# MovimientoALIM.net
KiCad netlist of a schematic drawn in EAGLE
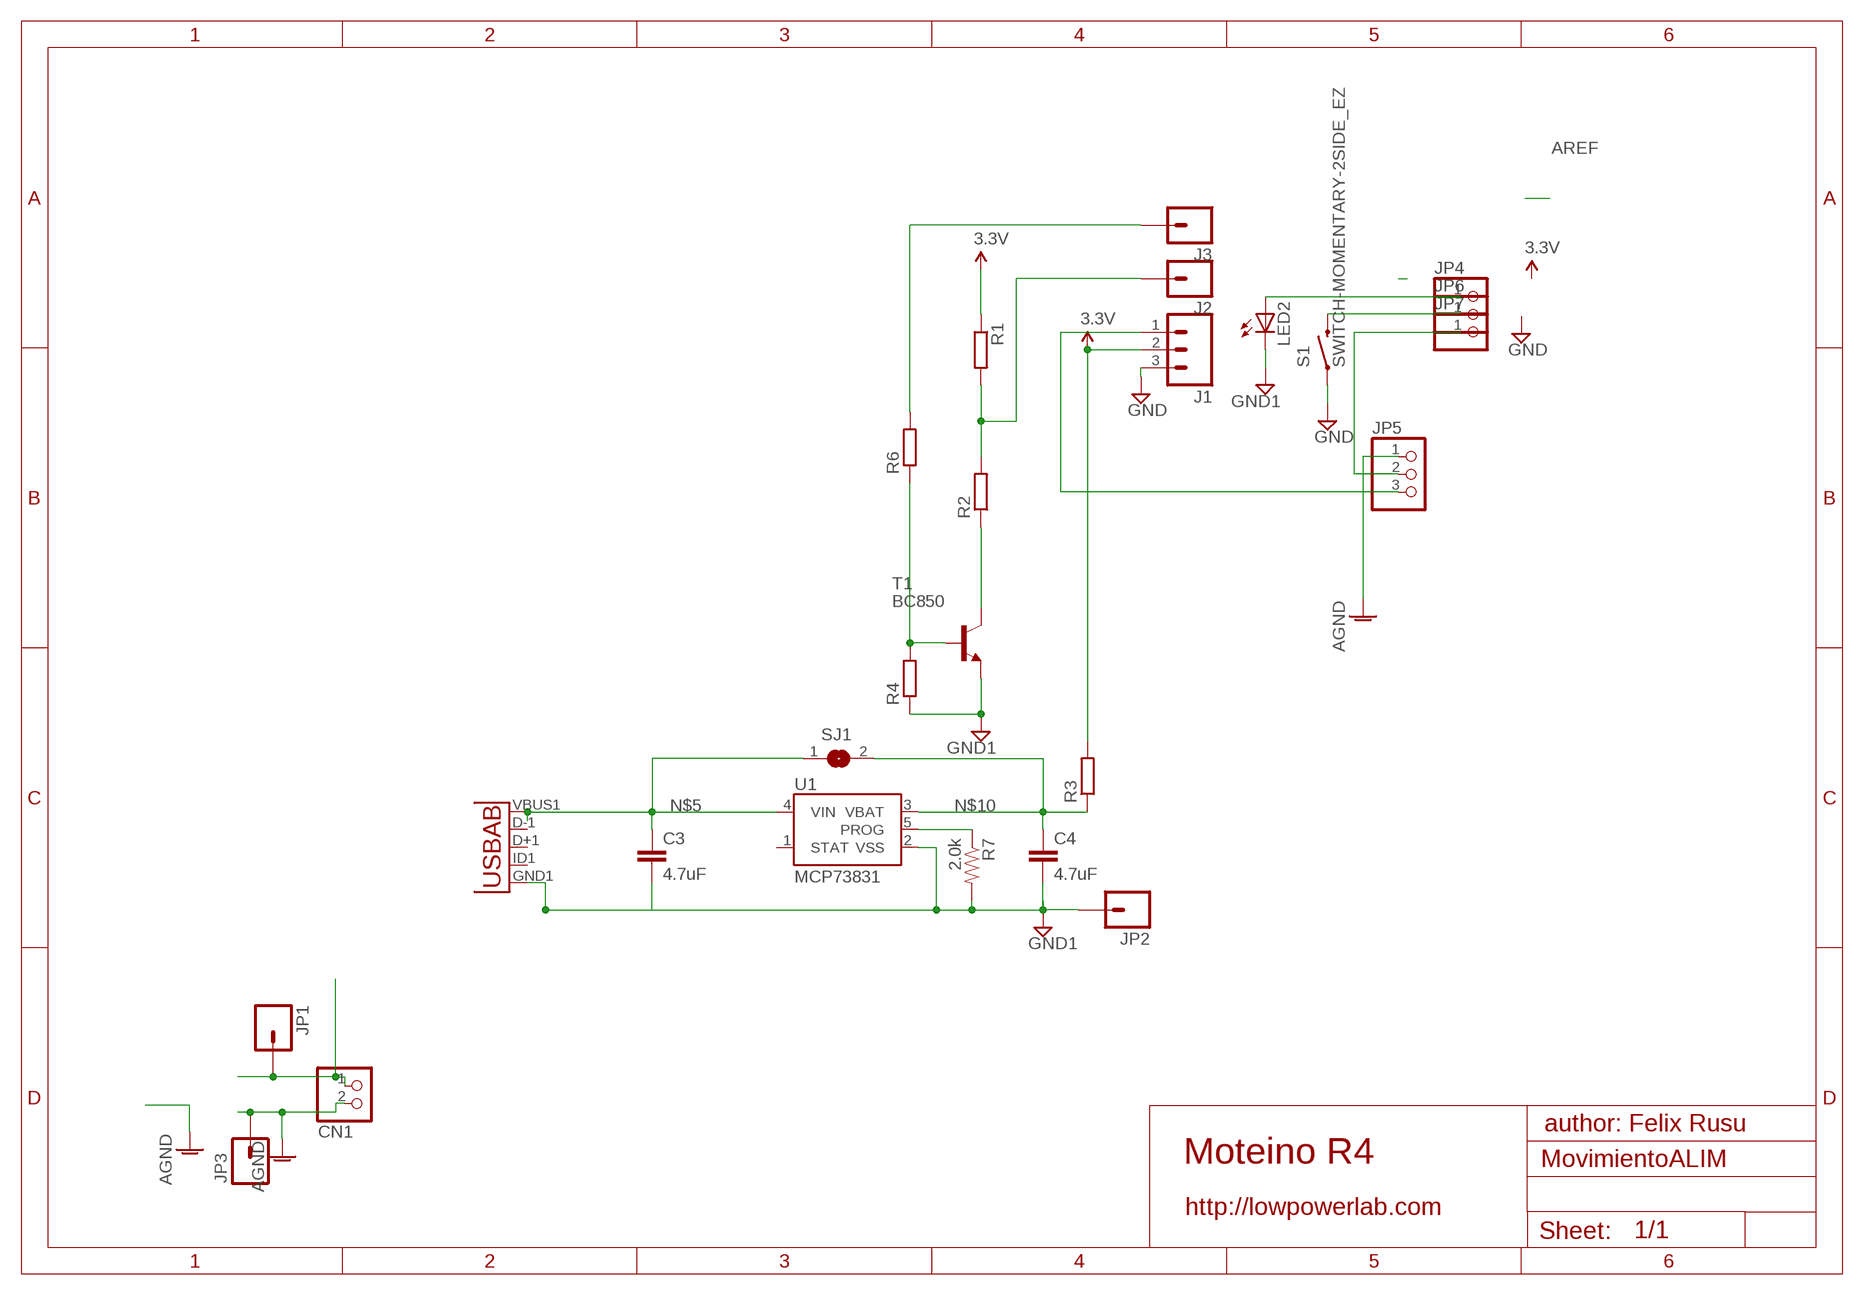
[diagram p0: schematic, sheet 1]

(export (version "E")
  (design (tool "Eeschema 10.0.6"))
  (components
    (comp (ref "C3")
      (value "4.7uF")
      (footprint "eagle-import:0603-CAP")
      (libsource (lib "eagle-import") (part "4.7UF-6.3V-10%(0603)0603"))
    )
    (comp (ref "C4")
      (value "4.7uF")
      (footprint "eagle-import:0603-CAP")
      (libsource (lib "eagle-import") (part "4.7UF-6.3V-10%(0603)0603"))
    )
    (comp (ref "CN1")
      (value "JST_2PIN-SMT")
      (footprint "eagle-import:JST-PH-2-SMT")
      (libsource (lib "eagle-import") (part "JST_2PIN-SMT"))
    )
    (comp (ref "J1")
      (value "M03PTH")
      (footprint "eagle-import:1X03")
      (libsource (lib "eagle-import") (part "M03PTH"))
    )
    (comp (ref "J2")
      (value "M01PTH")
      (footprint "eagle-import:1X01")
      (libsource (lib "eagle-import") (part "M01PTH"))
    )
    (comp (ref "J3")
      (value "M01PTH")
      (footprint "eagle-import:1X01")
      (libsource (lib "eagle-import") (part "M01PTH"))
    )
    (comp (ref "JP1")
      (value "M01PTH")
      (footprint "eagle-import:1X01")
      (libsource (lib "eagle-import") (part "M01PTH"))
    )
    (comp (ref "JP2")
      (value "M01PTH")
      (footprint "eagle-import:1X01")
      (libsource (lib "eagle-import") (part "M01PTH"))
    )
    (comp (ref "JP3")
      (value "M01PTH")
      (footprint "eagle-import:1X01")
      (libsource (lib "eagle-import") (part "M01PTH"))
    )
    (comp (ref "JP4")
      (value "PINHD-1X1")
      (footprint "eagle-import:1X01")
      (libsource (lib "eagle-import") (part "PINHD-1X1"))
    )
    (comp (ref "JP5")
      (value "PINHD-1X3")
      (footprint "eagle-import:1X03")
      (libsource (lib "eagle-import") (part "PINHD-1X3"))
    )
    (comp (ref "JP6")
      (value "PINHD-1X1")
      (footprint "eagle-import:1X01")
      (libsource (lib "eagle-import") (part "PINHD-1X1"))
    )
    (comp (ref "JP7")
      (value "PINHD-1X1")
      (footprint "eagle-import:1X01")
      (libsource (lib "eagle-import") (part "PINHD-1X1"))
    )
    (comp (ref "JP9")
      (value "Micro USB")
      (footprint "eagle-import:USB-AB-MICRO-SMD_V03")
      (libsource (lib "eagle-import") (part "USB-ABCONN-11794"))
    )
    (comp (ref "LED2")
      (value "LED3MM")
      (footprint "eagle-import:LED3MM")
      (libsource (lib "eagle-import") (part "LED3MM"))
    )
    (comp (ref "R1")
      (value "R-EU_0204/7")
      (footprint "eagle-import:0204_7")
      (libsource (lib "eagle-import") (part "R-EU_0204/7"))
    )
    (comp (ref "R2")
      (value "R-EU_0204/7")
      (footprint "eagle-import:0204_7")
      (libsource (lib "eagle-import") (part "R-EU_0204/7"))
    )
    (comp (ref "R3")
      (value "R-EU_M1206")
      (footprint "eagle-import:M1206")
      (libsource (lib "eagle-import") (part "R-EU_M1206"))
    )
    (comp (ref "R4")
      (value "R-EU_M1206")
      (footprint "eagle-import:M1206")
      (libsource (lib "eagle-import") (part "R-EU_M1206"))
    )
    (comp (ref "R6")
      (value "R-EU_M1206")
      (footprint "eagle-import:M1206")
      (libsource (lib "eagle-import") (part "R-EU_M1206"))
    )
    (comp (ref "R7")
      (value "2.0k")
      (footprint "eagle-import:0603-RES")
      (libsource (lib "eagle-import") (part "2.0KOHM1/10W5%(0603)"))
    )
    (comp (ref "S1")
      (value "SWITCH-MOMENTARY-2SIDE_EZ")
      (footprint "eagle-import:TACTILE-PTH-SIDEEZ")
      (libsource (lib "eagle-import") (part "SWITCH-MOMENTARY-2SIDE_EZ"))
    )
    (comp (ref "SJ1") (value "SJ") (footprint "eagle-import:SJ") (libsource (lib "eagle-import") (part "SJ")))
    (comp (ref "T1")
      (value "BC850")
      (footprint "eagle-import:SOT23")
      (libsource (lib "eagle-import") (part "BC850"))
    )
    (comp (ref "U1")
      (value "MCP73831")
      (footprint "eagle-import:SOT23-5")
      (libsource (lib "eagle-import") (part "MCP73831"))
    )
  )
  (nets
    (net (code "2") (name "/N$5") (class "Default")
      (node (ref "C3") (pin "1") (pinfunction "1_1") (pintype "passive"))
      (node (ref "JP9") (pin "VBUS1") (pinfunction "VBUS_VBUS1") (pintype "bidirectional"))
      (node (ref "SJ1") (pin "1") (pinfunction "1_1") (pintype "passive"))
      (node (ref "U1") (pin "4") (pinfunction "VIN_4") (pintype "power_in"))
    )
    (net (code "3") (name "/N$10") (class "Default")
      (node (ref "C4") (pin "1") (pinfunction "1_1") (pintype "passive"))
      (node (ref "R3") (pin "1") (pinfunction "1_1") (pintype "passive"))
      (node (ref "SJ1") (pin "2") (pinfunction "2_2") (pintype "passive"))
      (node (ref "U1") (pin "3") (pinfunction "VBAT_3") (pintype "power_in"))
    )
    (net (code "4") (name "3.3V") (class "Default")
      (node (ref "J1") (pin "2") (pinfunction "2_2") (pintype "passive"))
      (node (ref "R1") (pin "1") (pinfunction "1_1") (pintype "passive"))
      (node (ref "R3") (pin "2") (pinfunction "2_2") (pintype "passive"))
    )
    (net (code "5") (name "AGND") (class "Default")
      (node (ref "CN1") (pin "2") (pinfunction "1_2") (pintype "passive"))
      (node (ref "JP3") (pin "1") (pinfunction "1_1") (pintype "passive"))
      (node (ref "JP5") (pin "1") (pinfunction "1_1") (pintype "passive"))
    )
    (net (code "6") (name "GND") (class "Default")
      (node (ref "J1") (pin "3") (pinfunction "3_3") (pintype "passive"))
      (node (ref "S1") (pin "1") (pinfunction "1_1") (pintype "passive"))
    )
    (net (code "7") (name "GND1") (class "Default")
      (node (ref "C3") (pin "2") (pinfunction "2_2") (pintype "passive"))
      (node (ref "C4") (pin "2") (pinfunction "2_2") (pintype "passive"))
      (node (ref "JP2") (pin "1") (pinfunction "1_1") (pintype "passive"))
      (node (ref "JP9") (pin "GND1") (pinfunction "GND_GND1") (pintype "bidirectional"))
      (node (ref "LED2") (pin "K") (pinfunction "C_K") (pintype "passive"))
      (node (ref "R4") (pin "1") (pinfunction "1_1") (pintype "passive"))
      (node (ref "R7") (pin "2") (pinfunction "2_2") (pintype "passive"))
      (node (ref "T1") (pin "2") (pinfunction "E_2") (pintype "passive"))
      (node (ref "U1") (pin "2") (pinfunction "VSS_2") (pintype "power_in"))
    )
    (net (code "8") (name "Net-(CN1-2)") (class "Default")
      (node (ref "CN1") (pin "1") (pinfunction "2_1") (pintype "passive"))
      (node (ref "JP1") (pin "1") (pinfunction "1_1") (pintype "passive"))
    )
    (net (code "9") (name "Net-(J1-Pad1)") (class "Default")
      (node (ref "J1") (pin "1") (pinfunction "1_1") (pintype "passive"))
      (node (ref "JP5") (pin "3") (pinfunction "3_3") (pintype "passive"))
    )
    (net (code "10") (name "Net-(J2-Pad1)") (class "Default")
      (node (ref "J2") (pin "1") (pinfunction "1_1") (pintype "passive"))
      (node (ref "R1") (pin "2") (pinfunction "2_2") (pintype "passive"))
      (node (ref "R2") (pin "2") (pinfunction "2_2") (pintype "passive"))
    )
    (net (code "11") (name "Net-(J3-Pad1)") (class "Default")
      (node (ref "J3") (pin "1") (pinfunction "1_1") (pintype "passive"))
      (node (ref "R6") (pin "2") (pinfunction "2_2") (pintype "passive"))
    )
    (net (code "12") (name "Net-(JP4-Pad1)") (class "Default")
      (node (ref "JP4") (pin "1") (pinfunction "1_1") (pintype "passive"))
      (node (ref "LED2") (pin "A") (pinfunction "A_A") (pintype "passive"))
    )
    (net (code "13") (name "Net-(JP5-Pad2)") (class "Default")
      (node (ref "JP5") (pin "2") (pinfunction "2_2") (pintype "passive"))
      (node (ref "JP7") (pin "1") (pinfunction "1_1") (pintype "passive"))
    )
    (net (code "14") (name "Net-(JP6-Pad1)") (class "Default")
      (node (ref "JP6") (pin "1") (pinfunction "1_1") (pintype "passive"))
      (node (ref "S1") (pin "2") (pinfunction "2_2") (pintype "passive"))
    )
    (net (code "15") (name "Net-(T1-B)") (class "Default")
      (node (ref "R4") (pin "2") (pinfunction "2_2") (pintype "passive"))
      (node (ref "R6") (pin "1") (pinfunction "1_1") (pintype "passive"))
      (node (ref "T1") (pin "1") (pinfunction "B_1") (pintype "passive"))
    )
    (net (code "16") (name "Net-(T1-C)") (class "Default")
      (node (ref "R2") (pin "1") (pinfunction "1_1") (pintype "passive"))
      (node (ref "T1") (pin "3") (pinfunction "C_3") (pintype "passive"))
    )
    (net (code "17") (name "Net-(U1-PROG)") (class "Default")
      (node (ref "R7") (pin "1") (pinfunction "1_1") (pintype "passive"))
      (node (ref "U1") (pin "5") (pinfunction "PROG_5") (pintype "input"))
    )
    (net (code "18") (name "unconnected-(JP9-D+-PadD+1)") (class "Default")
      (node (ref "JP9") (pin "D+1") (pinfunction "D+_D+1") (pintype "bidirectional"))
    )
    (net (code "19") (name "unconnected-(JP9-D--PadD-1)") (class "Default")
      (node (ref "JP9") (pin "D-1") (pinfunction "D-_D-1") (pintype "bidirectional"))
    )
    (net (code "20") (name "unconnected-(JP9-USBID-PadID1)") (class "Default")
      (node (ref "JP9") (pin "ID1") (pinfunction "USBID_ID1") (pintype "bidirectional"))
    )
    (net (code "21") (name "unconnected-(U1-STAT-Pad1)") (class "Default")
      (node (ref "U1") (pin "1") (pinfunction "STAT_1") (pintype "output"))
    )
  )
)
